# PCB_4.net
KiCad netlist of a schematic drawn in Altium Designer
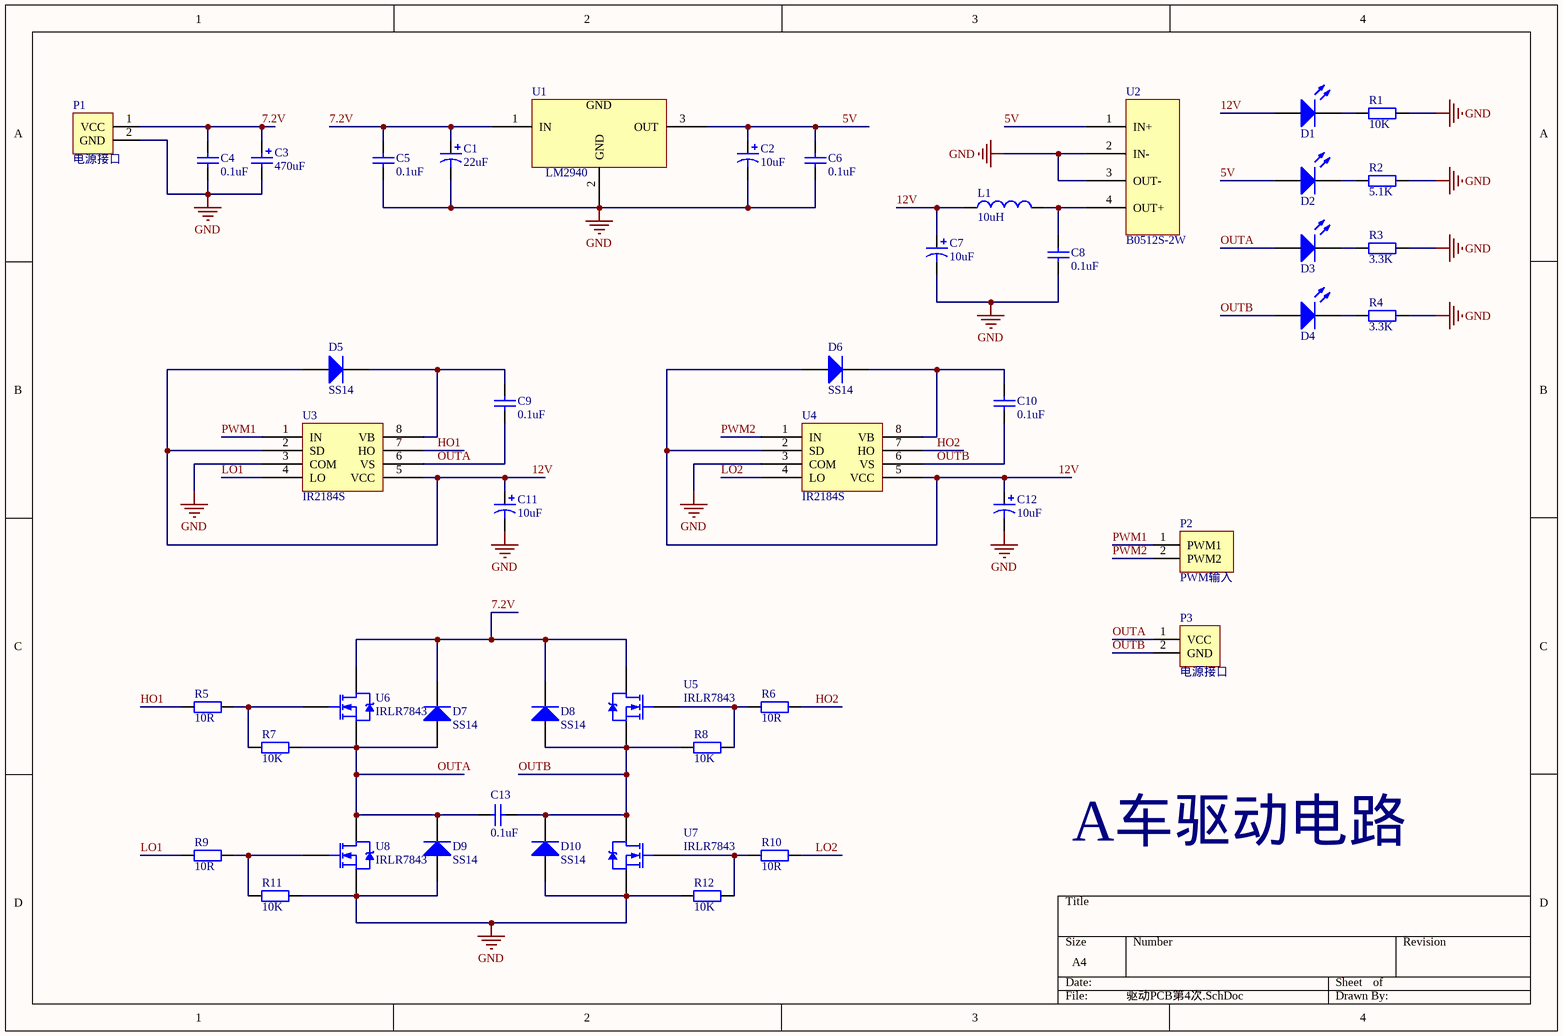
[diagram p0: 驱动PCB第4次.SchDoc]

(export (version "E")
  (design (tool "Eeschema 10.0.6"))
  (components
    (comp (ref "C1")
      (value "22uF")
      (footprint "22uf钽电容")
      (description "Polarized Capacitor (Axial)")
      (fields (field (name "Comment") "C-22uf钽电容"))
      (libsource (lib "SCH电机驱动库") (part "C-22uf钽电容"))
    )
    (comp (ref "C2")
      (value "10uF")
      (footprint "10uf钽电容")
      (description "Polarized Capacitor (Axial)")
      (fields (field (name "Comment") "C-10uf钽电容"))
      (libsource (lib "SCH电机驱动库") (part "C-10uf钽电容"))
    )
    (comp (ref "C3")
      (value "470uF")
      (footprint "C-470uF电解电容")
      (description "Polarized Capacitor (Surface Mount)")
      (fields (field (name "Comment") "C-470电解电容") (field (name "PUBLISHER") "Altium Limited"))
      (libsource (lib "SCH电机驱动库") (part "C-470电解电容"))
    )
    (comp (ref "C4")
      (value "0.1uF")
      (footprint "0805")
      (description "Capacitor")
      (fields (field (name "Comment") "C-0.1uf") (field (name "PUBLISHER") "Altium Limited"))
      (libsource (lib "SCH电机驱动库") (part "C-0.1uf"))
    )
    (comp (ref "C5")
      (value "0.1uF")
      (footprint "0805")
      (description "Capacitor")
      (fields (field (name "Comment") "C-0.1uf") (field (name "PUBLISHER") "Altium Limited"))
      (libsource (lib "SCH电机驱动库") (part "C-0.1uf"))
    )
    (comp (ref "C6")
      (value "0.1uF")
      (footprint "0805")
      (description "Capacitor")
      (fields (field (name "Comment") "C-0.1uf") (field (name "PUBLISHER") "Altium Limited"))
      (libsource (lib "SCH电机驱动库") (part "C-0.1uf"))
    )
    (comp (ref "C7")
      (value "10uF")
      (footprint "10uf钽电容")
      (description "Polarized Capacitor (Axial)")
      (fields (field (name "Comment") "C-10uf钽电容"))
      (libsource (lib "SCH电机驱动库") (part "C-10uf钽电容"))
    )
    (comp (ref "C8")
      (value "0.1uF")
      (footprint "0805")
      (description "Capacitor")
      (fields (field (name "Comment") "C-0.1uf") (field (name "PUBLISHER") "Altium Limited"))
      (libsource (lib "SCH电机驱动库") (part "C-0.1uf"))
    )
    (comp (ref "C9")
      (value "0.1uF")
      (footprint "0805")
      (description "Capacitor")
      (fields (field (name "Comment") "C-0.1uf") (field (name "PUBLISHER") "Altium Limited"))
      (libsource (lib "SCH电机驱动库") (part "C-0.1uf"))
    )
    (comp (ref "C10")
      (value "0.1uF")
      (footprint "0805")
      (description "Capacitor")
      (fields (field (name "Comment") "C-0.1uf") (field (name "PUBLISHER") "Altium Limited"))
      (libsource (lib "SCH电机驱动库") (part "C-0.1uf"))
    )
    (comp (ref "C11")
      (value "10uF")
      (footprint "10uf钽电容")
      (description "Polarized Capacitor (Axial)")
      (fields (field (name "Comment") "C-10uf钽电容"))
      (libsource (lib "SCH电机驱动库") (part "C-10uf钽电容"))
    )
    (comp (ref "C12")
      (value "10uF")
      (footprint "10uf钽电容")
      (description "Polarized Capacitor (Axial)")
      (fields (field (name "Comment") "C-10uf钽电容"))
      (libsource (lib "SCH电机驱动库") (part "C-10uf钽电容"))
    )
    (comp (ref "C13")
      (value "0.1uF")
      (footprint "0805")
      (description "Capacitor")
      (fields (field (name "Comment") "C-0.1uf") (field (name "PUBLISHER") "Altium Limited"))
      (libsource (lib "SCH电机驱动库") (part "C-0.1uf"))
    )
    (comp (ref "D1")
      (value "LED0")
      (footprint "LED")
      (description "Typical INFRARED GaAs LED")
      (fields (field (name "PUBLISHER") "Altium Limited"))
      (libsource (lib "SCH电机驱动库") (part "LED0"))
    )
    (comp (ref "D2")
      (value "LED0")
      (footprint "LED")
      (description "Typical INFRARED GaAs LED")
      (fields (field (name "PUBLISHER") "Altium Limited"))
      (libsource (lib "SCH电机驱动库") (part "LED0"))
    )
    (comp (ref "D3")
      (value "LED0")
      (footprint "LED")
      (description "Typical INFRARED GaAs LED")
      (fields (field (name "PUBLISHER") "Altium Limited"))
      (libsource (lib "SCH电机驱动库") (part "LED0"))
    )
    (comp (ref "D4")
      (value "LED0")
      (footprint "LED")
      (description "Typical INFRARED GaAs LED")
      (fields (field (name "PUBLISHER") "Altium Limited"))
      (libsource (lib "SCH电机驱动库") (part "LED0"))
    )
    (comp (ref "D5")
      (value "SS14")
      (footprint "二极管SS14 6032MM")
      (description "Default Diode")
      (libsource (lib "SCH电机驱动库") (part "Diode"))
    )
    (comp (ref "D6")
      (value "SS14")
      (footprint "二极管SS14 6032MM")
      (description "Default Diode")
      (libsource (lib "SCH电机驱动库") (part "Diode"))
    )
    (comp (ref "D7")
      (value "SS14")
      (footprint "二极管SS14 6032MM")
      (description "Default Diode")
      (libsource (lib "SCH电机驱动库") (part "Diode"))
    )
    (comp (ref "D8")
      (value "SS14")
      (footprint "二极管SS14 6032MM")
      (description "Default Diode")
      (libsource (lib "SCH电机驱动库") (part "Diode"))
    )
    (comp (ref "D9")
      (value "SS14")
      (footprint "二极管SS14 6032MM")
      (description "Default Diode")
      (libsource (lib "SCH电机驱动库") (part "Diode"))
    )
    (comp (ref "D10")
      (value "SS14")
      (footprint "二极管SS14 6032MM")
      (description "Default Diode")
      (libsource (lib "SCH电机驱动库") (part "Diode"))
    )
    (comp (ref "L1")
      (value "10uH")
      (footprint "0805")
      (description "Inductor")
      (fields (field (name "PUBLISHER") "Altium Limited"))
      (libsource (lib "SCH电机驱动库") (part "Inductor"))
    )
    (comp (ref "P1")
      (value "电源接口")
      (footprint "14AWG接口x2")
      (description "Header, 2-Pin")
      (fields (field (name "PUBLISHER") "Altium Limited"))
      (libsource (lib "SCH电机驱动库") (part "电源接口"))
    )
    (comp (ref "P2")
      (value "PWM输入")
      (footprint "PWM接口")
      (description "Header, 2-Pin")
      (fields (field (name "PUBLISHER") "Altium Limited"))
      (libsource (lib "SCH电机驱动库") (part "PWM输入"))
    )
    (comp (ref "P3")
      (value "电源接口")
      (footprint "14AWG接口x2")
      (description "Header, 2-Pin")
      (fields (field (name "PUBLISHER") "Altium Limited"))
      (libsource (lib "") (part "电源接口_1"))
    )
    (comp (ref "R1")
      (value "10K")
      (footprint "0805")
      (description "Resistor")
      (fields (field (name "Comment") "Res2") (field (name "PUBLISHER") "Altium Limited"))
      (libsource (lib "SCH电机驱动库") (part "Res2"))
    )
    (comp (ref "R2")
      (value "5.1K")
      (footprint "0805")
      (description "Resistor")
      (fields (field (name "Comment") "Res2") (field (name "PUBLISHER") "Altium Limited"))
      (libsource (lib "SCH电机驱动库") (part "Res2"))
    )
    (comp (ref "R3")
      (value "3.3K")
      (footprint "0805")
      (description "Resistor")
      (fields (field (name "Comment") "Res2") (field (name "PUBLISHER") "Altium Limited"))
      (libsource (lib "SCH电机驱动库") (part "Res2"))
    )
    (comp (ref "R4")
      (value "3.3K")
      (footprint "0805")
      (description "Resistor")
      (fields (field (name "Comment") "Res2") (field (name "PUBLISHER") "Altium Limited"))
      (libsource (lib "SCH电机驱动库") (part "Res2"))
    )
    (comp (ref "R5")
      (value "10R")
      (footprint "0805")
      (description "Resistor")
      (fields (field (name "Comment") "Res2") (field (name "PUBLISHER") "Altium Limited"))
      (libsource (lib "SCH电机驱动库") (part "Res2"))
    )
    (comp (ref "R6")
      (value "10R")
      (footprint "0805")
      (description "Resistor")
      (fields (field (name "Comment") "Res2") (field (name "PUBLISHER") "Altium Limited"))
      (libsource (lib "SCH电机驱动库") (part "Res2"))
    )
    (comp (ref "R7")
      (value "10K")
      (footprint "0805")
      (description "Resistor")
      (fields (field (name "Comment") "Res2") (field (name "PUBLISHER") "Altium Limited"))
      (libsource (lib "SCH电机驱动库") (part "Res2"))
    )
    (comp (ref "R8")
      (value "10K")
      (footprint "0805")
      (description "Resistor")
      (fields (field (name "Comment") "Res2") (field (name "PUBLISHER") "Altium Limited"))
      (libsource (lib "SCH电机驱动库") (part "Res2"))
    )
    (comp (ref "R9")
      (value "10R")
      (footprint "0805")
      (description "Resistor")
      (fields (field (name "Comment") "Res2") (field (name "PUBLISHER") "Altium Limited"))
      (libsource (lib "SCH电机驱动库") (part "Res2"))
    )
    (comp (ref "R10")
      (value "10R")
      (footprint "0805")
      (description "Resistor")
      (fields (field (name "Comment") "Res2") (field (name "PUBLISHER") "Altium Limited"))
      (libsource (lib "SCH电机驱动库") (part "Res2"))
    )
    (comp (ref "R11")
      (value "10K")
      (footprint "0805")
      (description "Resistor")
      (fields (field (name "Comment") "Res2") (field (name "PUBLISHER") "Altium Limited"))
      (libsource (lib "SCH电机驱动库") (part "Res2"))
    )
    (comp (ref "R12")
      (value "10K")
      (footprint "0805")
      (description "Resistor")
      (fields (field (name "Comment") "Res2") (field (name "PUBLISHER") "Altium Limited"))
      (libsource (lib "SCH电机驱动库") (part "Res2"))
    )
    (comp (ref "U1")
      (value "LM2940")
      (footprint "lm2940")
      (description "1A Low Dropout Regulator")
      (libsource (lib "SCH电机驱动库") (part "LM2940"))
    )
    (comp (ref "U2")
      (value "B0512S-2W")
      (footprint "MICRODC5-15")
      (libsource (lib "SCH电机驱动库") (part "B0512S-2W"))
    )
    (comp (ref "U3") (value "IR2184S") (footprint "IR2184S") (libsource (lib "SCH电机驱动库") (part "IR2184S")))
    (comp (ref "U4") (value "IR2184S") (footprint "IR2184S") (libsource (lib "SCH电机驱动库") (part "IR2184S")))
    (comp (ref "U5")
      (value "IRLR7843")
      (footprint "IRLR7843")
      (description "HEXFET Power MOSFET")
      (fields (field (name "PUBLISHER") "Altium Limited"))
      (libsource (lib "SCH电机驱动库") (part "IRLR7843"))
    )
    (comp (ref "U6")
      (value "IRLR7843")
      (footprint "IRLR7843")
      (description "HEXFET Power MOSFET")
      (fields (field (name "PUBLISHER") "Altium Limited"))
      (libsource (lib "SCH电机驱动库") (part "IRLR7843"))
    )
    (comp (ref "U7")
      (value "IRLR7843")
      (footprint "IRLR7843")
      (description "HEXFET Power MOSFET")
      (fields (field (name "PUBLISHER") "Altium Limited"))
      (libsource (lib "SCH电机驱动库") (part "IRLR7843"))
    )
    (comp (ref "U8")
      (value "IRLR7843")
      (footprint "IRLR7843")
      (description "HEXFET Power MOSFET")
      (fields (field (name "PUBLISHER") "Altium Limited"))
      (libsource (lib "SCH电机驱动库") (part "IRLR7843"))
    )
  )
  (nets
    (net (code "1") (name "/5V") (class "Default")
      (node (ref "C2") (pin "1") (pinfunction "1_1") (pintype "passive"))
      (node (ref "C6") (pin "2") (pinfunction "2_2") (pintype "passive"))
      (node (ref "D2") (pin "1") (pinfunction "A_1") (pintype "passive"))
      (node (ref "U1") (pin "3") (pinfunction "OUT_3") (pintype "passive"))
      (node (ref "U2") (pin "1") (pinfunction "IN+_1") (pintype "passive"))
    )
    (net (code "2") (name "/7.2V") (class "Default")
      (node (ref "C1") (pin "1") (pinfunction "1_1") (pintype "passive"))
      (node (ref "C3") (pin "1") (pinfunction "1_1") (pintype "passive"))
      (node (ref "C4") (pin "1") (pinfunction "1_1") (pintype "passive"))
      (node (ref "C5") (pin "2") (pinfunction "2_2") (pintype "passive"))
      (node (ref "D7") (pin "2") (pinfunction "K_2") (pintype "passive"))
      (node (ref "D8") (pin "2") (pinfunction "K_2") (pintype "passive"))
      (node (ref "P1") (pin "1") (pinfunction "VCC_1") (pintype "passive"))
      (node (ref "U1") (pin "1") (pinfunction "IN_1") (pintype "passive"))
      (node (ref "U5") (pin "2") (pinfunction "D_2") (pintype "passive"))
      (node (ref "U6") (pin "2") (pinfunction "D_2") (pintype "passive"))
    )
    (net (code "3") (name "/12V") (class "Default")
      (node (ref "C11") (pin "1") (pinfunction "1_1") (pintype "passive"))
      (node (ref "C12") (pin "1") (pinfunction "1_1") (pintype "passive"))
      (node (ref "C7") (pin "1") (pinfunction "1_1") (pintype "passive"))
      (node (ref "D1") (pin "1") (pinfunction "A_1") (pintype "passive"))
      (node (ref "D5") (pin "1") (pinfunction "A_1") (pintype "passive"))
      (node (ref "D6") (pin "1") (pinfunction "A_1") (pintype "passive"))
      (node (ref "L1") (pin "1") (pinfunction "1_1") (pintype "passive"))
      (node (ref "U3") (pin "2") (pinfunction "SD_2") (pintype "passive"))
      (node (ref "U3") (pin "5") (pinfunction "VCC_5") (pintype "passive"))
      (node (ref "U4") (pin "2") (pinfunction "SD_2") (pintype "passive"))
      (node (ref "U4") (pin "5") (pinfunction "VCC_5") (pintype "passive"))
    )
    (net (code "4") (name "/HO1") (class "Default")
      (node (ref "R5") (pin "1") (pinfunction "1_1") (pintype "passive"))
      (node (ref "U3") (pin "7") (pinfunction "HO_7") (pintype "passive"))
    )
    (net (code "5") (name "/HO2") (class "Default")
      (node (ref "R6") (pin "2") (pinfunction "2_2") (pintype "passive"))
      (node (ref "U4") (pin "7") (pinfunction "HO_7") (pintype "passive"))
    )
    (net (code "6") (name "/LO1") (class "Default")
      (node (ref "R9") (pin "1") (pinfunction "1_1") (pintype "passive"))
      (node (ref "U3") (pin "4") (pinfunction "LO_4") (pintype "passive"))
    )
    (net (code "7") (name "/LO2") (class "Default")
      (node (ref "R10") (pin "2") (pinfunction "2_2") (pintype "passive"))
      (node (ref "U4") (pin "4") (pinfunction "LO_4") (pintype "passive"))
    )
    (net (code "8") (name "/OUTA") (class "Default")
      (node (ref "C13") (pin "1") (pinfunction "1_1") (pintype "passive"))
      (node (ref "C9") (pin "1") (pinfunction "1_1") (pintype "passive"))
      (node (ref "D3") (pin "1") (pinfunction "A_1") (pintype "passive"))
      (node (ref "D7") (pin "1") (pinfunction "A_1") (pintype "passive"))
      (node (ref "D9") (pin "2") (pinfunction "K_2") (pintype "passive"))
      (node (ref "P3") (pin "1") (pinfunction "VCC_1") (pintype "passive"))
      (node (ref "R7") (pin "2") (pinfunction "2_2") (pintype "passive"))
      (node (ref "U3") (pin "6") (pinfunction "VS_6") (pintype "passive"))
      (node (ref "U6") (pin "3") (pinfunction "S_3") (pintype "passive"))
      (node (ref "U8") (pin "2") (pinfunction "D_2") (pintype "passive"))
    )
    (net (code "9") (name "/OUTB") (class "Default")
      (node (ref "C10") (pin "1") (pinfunction "1_1") (pintype "passive"))
      (node (ref "C13") (pin "2") (pinfunction "2_2") (pintype "passive"))
      (node (ref "D10") (pin "2") (pinfunction "K_2") (pintype "passive"))
      (node (ref "D4") (pin "1") (pinfunction "A_1") (pintype "passive"))
      (node (ref "D8") (pin "1") (pinfunction "A_1") (pintype "passive"))
      (node (ref "P3") (pin "2") (pinfunction "GND_2") (pintype "passive"))
      (node (ref "R8") (pin "1") (pinfunction "1_1") (pintype "passive"))
      (node (ref "U4") (pin "6") (pinfunction "VS_6") (pintype "passive"))
      (node (ref "U5") (pin "3") (pinfunction "S_3") (pintype "passive"))
      (node (ref "U7") (pin "2") (pinfunction "D_2") (pintype "passive"))
    )
    (net (code "10") (name "/PWM1") (class "Default")
      (node (ref "P2") (pin "1") (pinfunction "PWM1_1") (pintype "passive"))
      (node (ref "U3") (pin "1") (pinfunction "IN_1") (pintype "passive"))
    )
    (net (code "11") (name "/PWM2") (class "Default")
      (node (ref "P2") (pin "2") (pinfunction "PWM2_2") (pintype "passive"))
      (node (ref "U4") (pin "1") (pinfunction "IN_1") (pintype "passive"))
    )
    (net (code "12") (name "GND") (class "Default")
      (node (ref "C1") (pin "2") (pinfunction "2_2") (pintype "passive"))
      (node (ref "C11") (pin "2") (pinfunction "2_2") (pintype "passive"))
      (node (ref "C12") (pin "2") (pinfunction "2_2") (pintype "passive"))
      (node (ref "C2") (pin "2") (pinfunction "2_2") (pintype "passive"))
      (node (ref "C3") (pin "2") (pinfunction "2_2") (pintype "passive"))
      (node (ref "C4") (pin "2") (pinfunction "2_2") (pintype "passive"))
      (node (ref "C5") (pin "1") (pinfunction "1_1") (pintype "passive"))
      (node (ref "C6") (pin "1") (pinfunction "1_1") (pintype "passive"))
      (node (ref "C7") (pin "2") (pinfunction "2_2") (pintype "passive"))
      (node (ref "C8") (pin "1") (pinfunction "1_1") (pintype "passive"))
      (node (ref "D10") (pin "1") (pinfunction "A_1") (pintype "passive"))
      (node (ref "D9") (pin "1") (pinfunction "A_1") (pintype "passive"))
      (node (ref "P1") (pin "2") (pinfunction "GND_2") (pintype "passive"))
      (node (ref "R1") (pin "2") (pinfunction "2_2") (pintype "passive"))
      (node (ref "R11") (pin "2") (pinfunction "2_2") (pintype "passive"))
      (node (ref "R12") (pin "1") (pinfunction "1_1") (pintype "passive"))
      (node (ref "R2") (pin "2") (pinfunction "2_2") (pintype "passive"))
      (node (ref "R3") (pin "2") (pinfunction "2_2") (pintype "passive"))
      (node (ref "R4") (pin "2") (pinfunction "2_2") (pintype "passive"))
      (node (ref "U1") (pin "2") (pinfunction "GND_2") (pintype "passive"))
      (node (ref "U2") (pin "2") (pinfunction "IN-_2") (pintype "passive"))
      (node (ref "U2") (pin "3") (pinfunction "OUT-_3") (pintype "passive"))
      (node (ref "U3") (pin "3") (pinfunction "COM_3") (pintype "passive"))
      (node (ref "U4") (pin "3") (pinfunction "COM_3") (pintype "passive"))
      (node (ref "U7") (pin "3") (pinfunction "S_3") (pintype "passive"))
      (node (ref "U8") (pin "3") (pinfunction "S_3") (pintype "passive"))
    )
    (net (code "13") (name "Net-(D1-K)") (class "Default")
      (node (ref "D1") (pin "2") (pinfunction "K_2") (pintype "passive"))
      (node (ref "R1") (pin "1") (pinfunction "1_1") (pintype "passive"))
    )
    (net (code "14") (name "Net-(D2-K)") (class "Default")
      (node (ref "D2") (pin "2") (pinfunction "K_2") (pintype "passive"))
      (node (ref "R2") (pin "1") (pinfunction "1_1") (pintype "passive"))
    )
    (net (code "15") (name "Net-(D3-K)") (class "Default")
      (node (ref "D3") (pin "2") (pinfunction "K_2") (pintype "passive"))
      (node (ref "R3") (pin "1") (pinfunction "1_1") (pintype "passive"))
    )
    (net (code "16") (name "Net-(D4-K)") (class "Default")
      (node (ref "D4") (pin "2") (pinfunction "K_2") (pintype "passive"))
      (node (ref "R4") (pin "1") (pinfunction "1_1") (pintype "passive"))
    )
    (net (code "17") (name "Net-(D5-K)") (class "Default")
      (node (ref "C9") (pin "2") (pinfunction "2_2") (pintype "passive"))
      (node (ref "D5") (pin "2") (pinfunction "K_2") (pintype "passive"))
      (node (ref "U3") (pin "8") (pinfunction "VB_8") (pintype "passive"))
    )
    (net (code "18") (name "Net-(D6-K)") (class "Default")
      (node (ref "C10") (pin "2") (pinfunction "2_2") (pintype "passive"))
      (node (ref "D6") (pin "2") (pinfunction "K_2") (pintype "passive"))
      (node (ref "U4") (pin "8") (pinfunction "VB_8") (pintype "passive"))
    )
    (net (code "19") (name "Net-(U2-OUT+)") (class "Default")
      (node (ref "C8") (pin "2") (pinfunction "2_2") (pintype "passive"))
      (node (ref "L1") (pin "2") (pinfunction "2_2") (pintype "passive"))
      (node (ref "U2") (pin "4") (pinfunction "OUT+_4") (pintype "passive"))
    )
    (net (code "20") (name "Net-(U5-G)") (class "Default")
      (node (ref "R6") (pin "1") (pinfunction "1_1") (pintype "passive"))
      (node (ref "R8") (pin "2") (pinfunction "2_2") (pintype "passive"))
      (node (ref "U5") (pin "1") (pinfunction "G_1") (pintype "passive"))
    )
    (net (code "21") (name "Net-(U6-G)") (class "Default")
      (node (ref "R5") (pin "2") (pinfunction "2_2") (pintype "passive"))
      (node (ref "R7") (pin "1") (pinfunction "1_1") (pintype "passive"))
      (node (ref "U6") (pin "1") (pinfunction "G_1") (pintype "passive"))
    )
    (net (code "22") (name "Net-(U7-G)") (class "Default")
      (node (ref "R10") (pin "1") (pinfunction "1_1") (pintype "passive"))
      (node (ref "R12") (pin "2") (pinfunction "2_2") (pintype "passive"))
      (node (ref "U7") (pin "1") (pinfunction "G_1") (pintype "passive"))
    )
    (net (code "23") (name "Net-(U8-G)") (class "Default")
      (node (ref "R11") (pin "1") (pinfunction "1_1") (pintype "passive"))
      (node (ref "R9") (pin "2") (pinfunction "2_2") (pintype "passive"))
      (node (ref "U8") (pin "1") (pinfunction "G_1") (pintype "passive"))
    )
  )
)
